# SCH_Dashboy_camera_NiMH_2023-03-21.net
KiCad netlist of a schematic drawn in EasyEDA
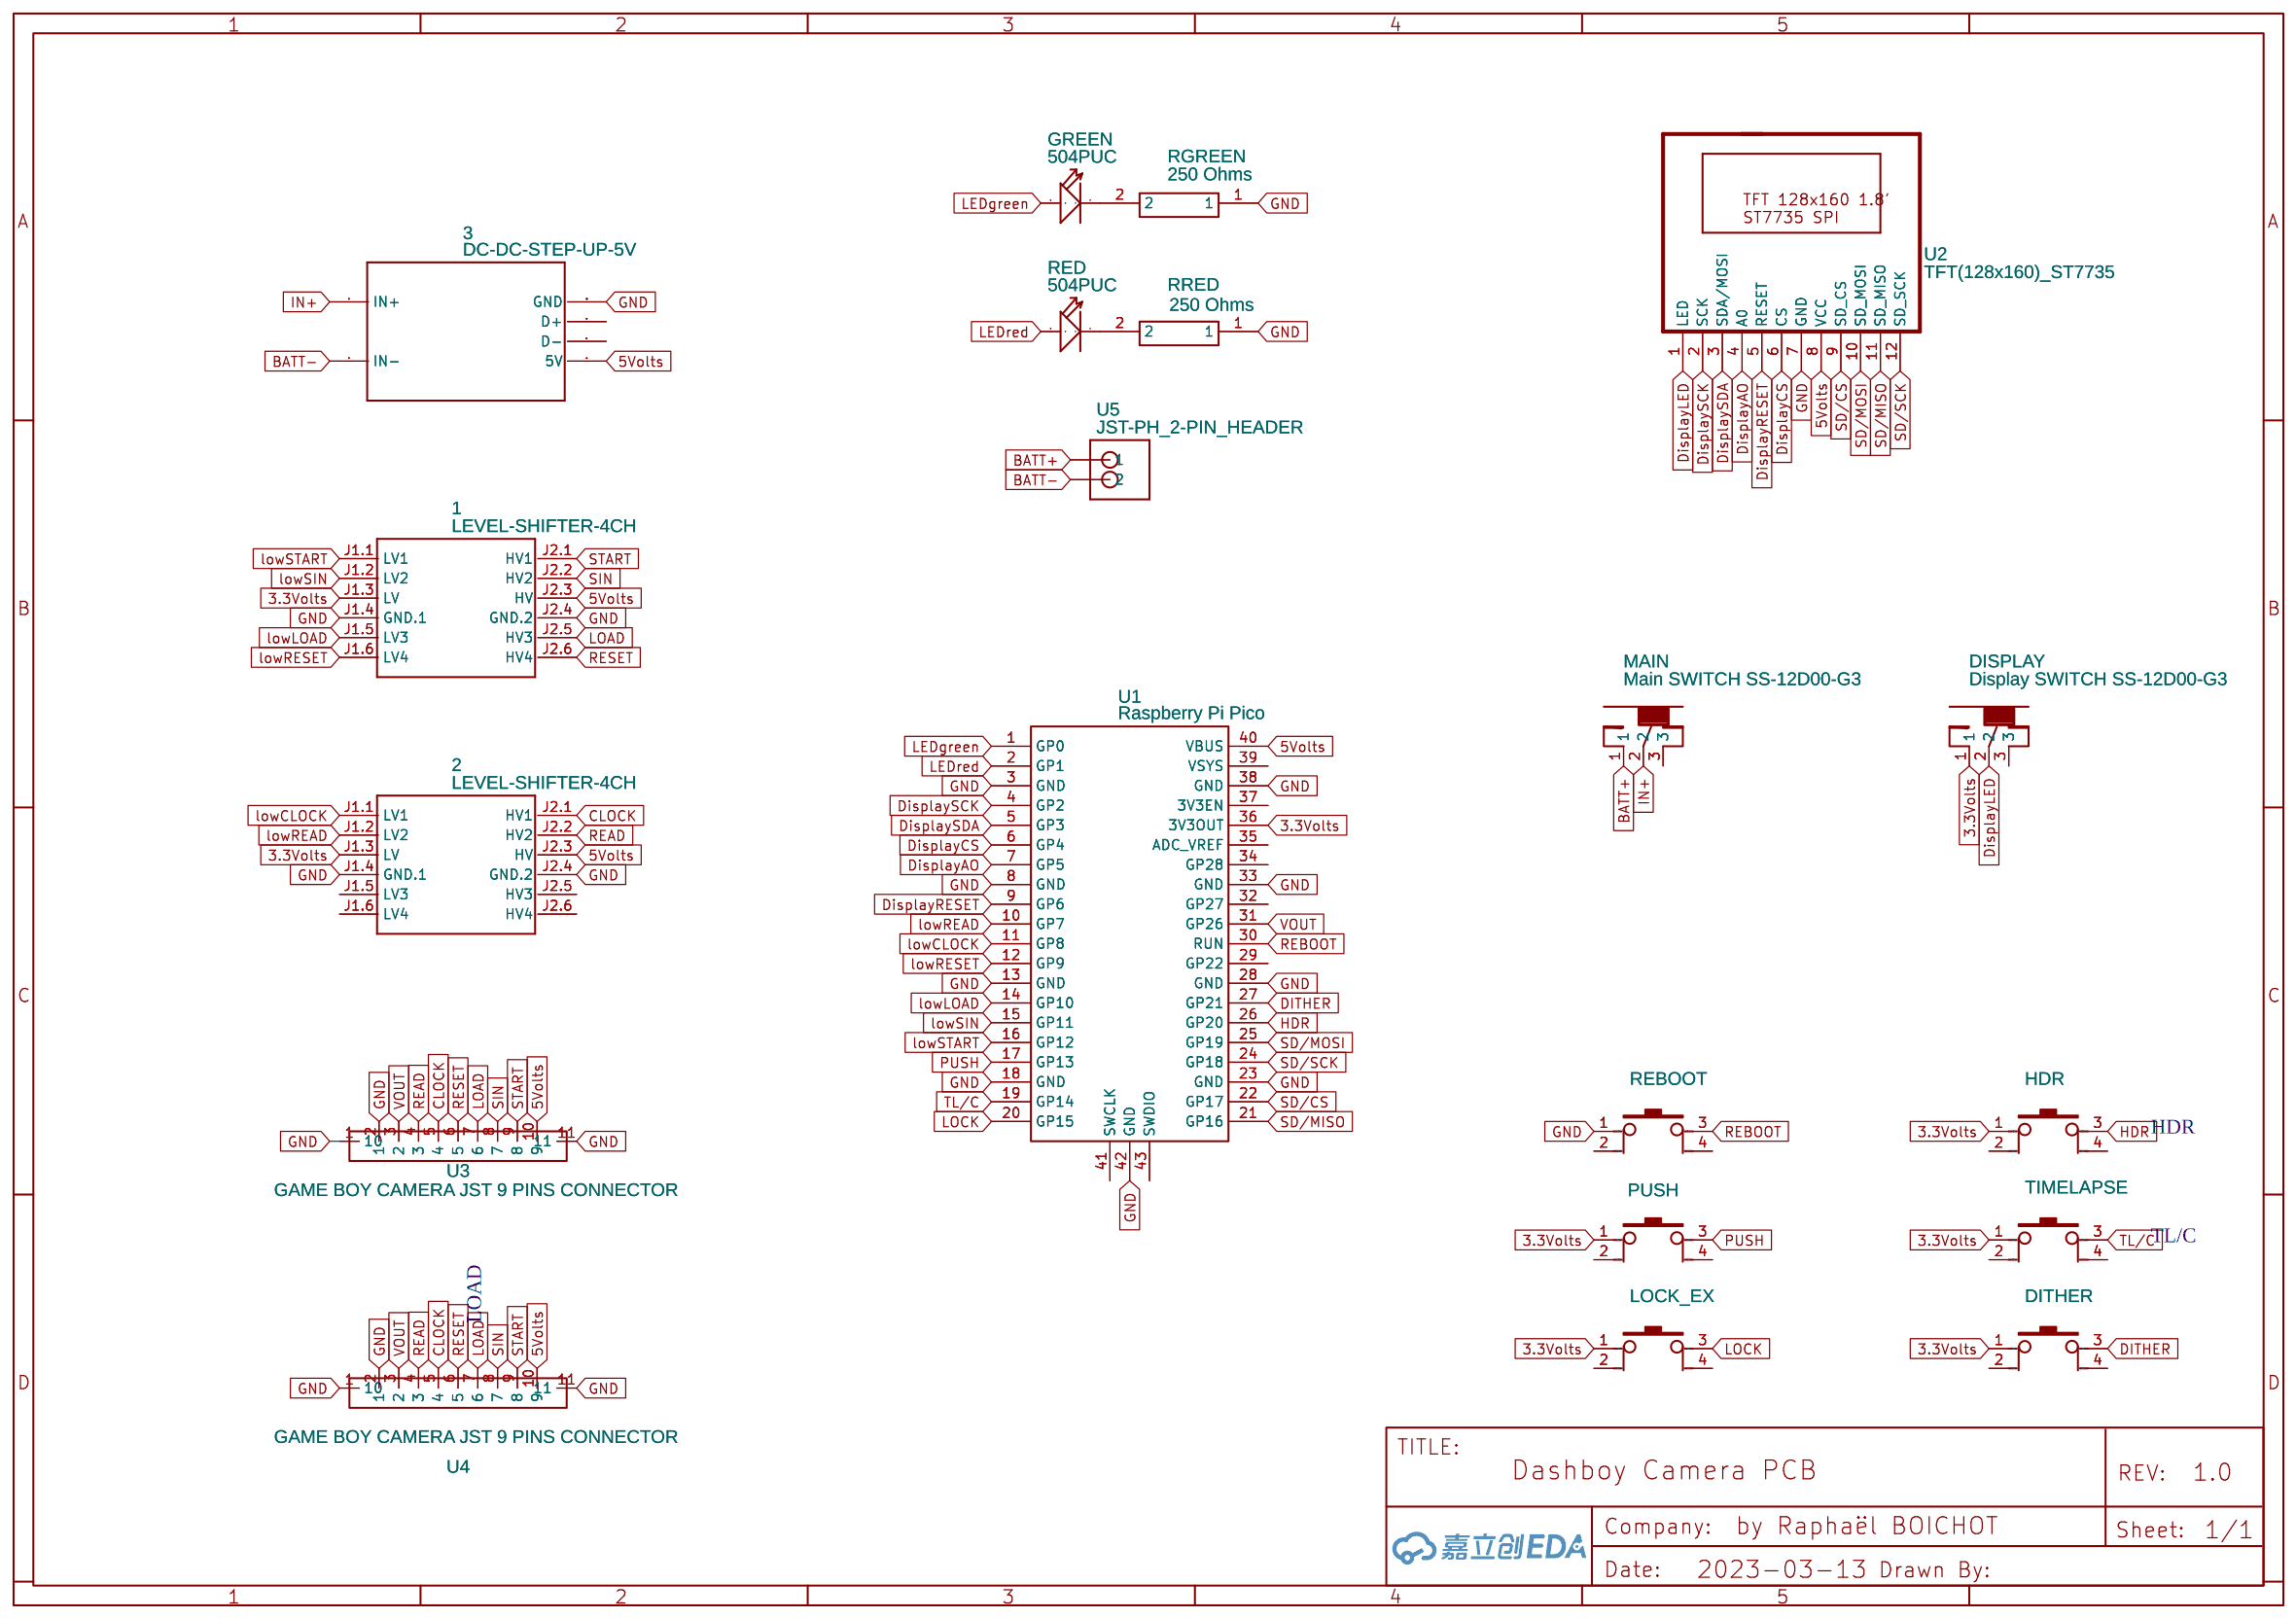
[diagram p0: schematic sheet]

(export (version "E")
  (design (tool "Eeschema 10.0.6"))
  (components
    (comp (ref "1") (value "LEVEL-SHIFTER-4CH") (libsource (lib "") (part "LEVEL-SHIFTER-4CH")))
    (comp (ref "2") (value "LEVEL-SHIFTER-4CH") (libsource (lib "") (part "LEVEL-SHIFTER-4CH")))
    (comp (ref "3") (value "DC-DC-STEP-UP-5V") (libsource (lib "") (part "DC-DC-STEP-UP-5V")))
    (comp (ref "DISPLAY")
      (value "Display SWITCH SS-12D00-G3")
      (fields (field (name "BOM_Manufacturer Part") "TOGGLE SWITCH SS-12D00-G3"))
      (libsource (lib "") (part "TOGGLE SWITCH SS-12D00-G3_1"))
    )
    (comp (ref "DITHER")
      (value "BoutonPoussoir")
      (fields
        (field (name "BOM_Manufacturer Part") "button6*6*8")
        (field (name "BOM_Supplier Part") "C59982")
      )
      (libsource (lib "") (part "BoutonPoussoir_5"))
    )
    (comp (ref "GREEN") (value "504PUC") (libsource (lib "") (part "504PUC_1")))
    (comp (ref "HDR")
      (value "BoutonPoussoir")
      (fields
        (field (name "BOM_Manufacturer Part") "button6*6*8")
        (field (name "BOM_Supplier Part") "C59982")
      )
      (libsource (lib "") (part "BoutonPoussoir_4"))
    )
    (comp (ref "LOCK_EX")
      (value "BoutonPoussoir")
      (fields
        (field (name "BOM_Manufacturer Part") "button6*6*8")
        (field (name "BOM_Supplier Part") "C59982")
      )
      (libsource (lib "") (part "BoutonPoussoir_2"))
    )
    (comp (ref "MAIN")
      (value "Main SWITCH SS-12D00-G3")
      (fields (field (name "BOM_Manufacturer Part") "TOGGLE SWITCH SS-12D00-G3"))
      (libsource (lib "") (part "TOGGLE SWITCH SS-12D00-G3"))
    )
    (comp (ref "PUSH")
      (value "BoutonPoussoir")
      (fields
        (field (name "BOM_Manufacturer Part") "button6*6*8")
        (field (name "BOM_Supplier Part") "C59982")
      )
      (libsource (lib "") (part "BoutonPoussoir_1"))
    )
    (comp (ref "REBOOT")
      (value "BoutonPoussoir")
      (fields
        (field (name "BOM_Manufacturer Part") "button6*6*8")
        (field (name "BOM_Supplier Part") "C59982")
      )
      (libsource (lib "") (part "BoutonPoussoir"))
    )
    (comp (ref "RED") (value "504PUC") (libsource (lib "") (part "504PUC")))
    (comp (ref "RGREEN") (value "250 Ohms") (libsource (lib "") (part "RESITOR")))
    (comp (ref "RRED") (value "250 Ohms") (libsource (lib "") (part "RESITOR_1")))
    (comp (ref "TIMELAPSE")
      (value "BoutonPoussoir")
      (fields
        (field (name "BOM_Manufacturer Part") "button6*6*8")
        (field (name "BOM_Supplier Part") "C59982")
      )
      (libsource (lib "") (part "BoutonPoussoir_3"))
    )
    (comp (ref "U1") (value "Raspberry Pi Pico") (libsource (lib "") (part "Raspberry Pi Pico")))
    (comp (ref "U2") (value "TFT(128x160)_ST7735") (libsource (lib "") (part "TFT(128x160)_ST7735")))
    (comp (ref "U3")
      (value "GAME BOY CAMERA JST 9 PINS CONNECTOR")
      (libsource (lib "") (part "GAME BOY CAMERA JST 9 PINS CONNECTOR"))
    )
    (comp (ref "U4")
      (value "GAME BOY CAMERA JST 9 PINS CONNECTOR")
      (libsource (lib "") (part "GAME BOY CAMERA JST 9 PINS CONNECTOR"))
    )
    (comp (ref "U5") (value "JST-PH_2-PIN_HEADER") (libsource (lib "") (part "JST-PH_2-PIN_HEADER")))
  )
  (nets
    (net (code "1") (name "3.3Volts") (class "Default")
      (node (ref "1") (pin "J1.3") (pinfunction "LV_J1.3") (pintype "bidirectional"))
      (node (ref "2") (pin "J1.3") (pinfunction "LV_J1.3") (pintype "bidirectional"))
      (node (ref "DISPLAY") (pin "1") (pinfunction "1_1") (pintype "bidirectional"))
      (node (ref "DITHER") (pin "1") (pinfunction "1_1") (pintype "input"))
      (node (ref "HDR") (pin "1") (pinfunction "1_1") (pintype "input"))
      (node (ref "LOCK_EX") (pin "1") (pinfunction "1_1") (pintype "input"))
      (node (ref "PUSH") (pin "1") (pinfunction "1_1") (pintype "input"))
      (node (ref "TIMELAPSE") (pin "1") (pinfunction "1_1") (pintype "input"))
      (node (ref "U1") (pin "36") (pinfunction "3V3OUT_36") (pintype "unspecified"))
    )
    (net (code "2") (name "5Volts") (class "Default")
      (node (ref "1") (pin "J2.3") (pinfunction "HV_J2.3") (pintype "bidirectional"))
      (node (ref "2") (pin "J2.3") (pinfunction "HV_J2.3") (pintype "bidirectional"))
      (node (ref "3") (pin "5V") (pinfunction "5V_5V") (pintype "bidirectional"))
      (node (ref "U1") (pin "40") (pinfunction "VBUS_40") (pintype "unspecified"))
      (node (ref "U2") (pin "8") (pinfunction "VCC_8") (pintype "input"))
      (node (ref "U3") (pin "10") (pinfunction "9_10") (pintype "unspecified"))
      (node (ref "U4") (pin "10") (pinfunction "9_10") (pintype "unspecified"))
    )
    (net (code "3") (name "BATT+") (class "Default")
      (node (ref "MAIN") (pin "1") (pinfunction "1_1") (pintype "bidirectional"))
      (node (ref "U5") (pin "P1") (pinfunction "1_P1") (pintype "unspecified"))
    )
    (net (code "4") (name "BATT-") (class "Default")
      (node (ref "3") (pin "IN-") (pinfunction "IN-_IN-") (pintype "bidirectional"))
      (node (ref "U5") (pin "P2") (pinfunction "2_P2") (pintype "unspecified"))
    )
    (net (code "5") (name "CLOCK") (class "Default")
      (node (ref "2") (pin "J2.1") (pinfunction "HV1_J2.1") (pintype "bidirectional"))
      (node (ref "U3") (pin "5") (pinfunction "4_5") (pintype "unspecified"))
      (node (ref "U4") (pin "5") (pinfunction "4_5") (pintype "unspecified"))
    )
    (net (code "6") (name "DITHER") (class "Default")
      (node (ref "DITHER") (pin "3") (pinfunction "3_3") (pintype "input"))
      (node (ref "U1") (pin "27") (pinfunction "GP21_27") (pintype "unspecified"))
    )
    (net (code "7") (name "DisplayAO") (class "Default")
      (node (ref "U1") (pin "7") (pinfunction "GP5_7") (pintype "unspecified"))
      (node (ref "U2") (pin "4") (pinfunction "A0_4") (pintype "input"))
    )
    (net (code "8") (name "DisplayCS") (class "Default")
      (node (ref "U1") (pin "6") (pinfunction "GP4_6") (pintype "unspecified"))
      (node (ref "U2") (pin "6") (pinfunction "CS_6") (pintype "input"))
    )
    (net (code "9") (name "DisplayLED") (class "Default")
      (node (ref "DISPLAY") (pin "2") (pinfunction "2_2") (pintype "bidirectional"))
      (node (ref "U2") (pin "1") (pinfunction "LED_1") (pintype "passive"))
    )
    (net (code "10") (name "DisplayRESET") (class "Default")
      (node (ref "U1") (pin "9") (pinfunction "GP6_9") (pintype "unspecified"))
      (node (ref "U2") (pin "5") (pinfunction "RESET_5") (pintype "input"))
    )
    (net (code "11") (name "DisplaySCK") (class "Default")
      (node (ref "U1") (pin "4") (pinfunction "GP2_4") (pintype "unspecified"))
      (node (ref "U2") (pin "2") (pinfunction "SCK_2") (pintype "output"))
    )
    (net (code "12") (name "DisplaySDA") (class "Default")
      (node (ref "U1") (pin "5") (pinfunction "GP3_5") (pintype "unspecified"))
      (node (ref "U2") (pin "3") (pinfunction "SDA/MOSI_3") (pintype "input"))
    )
    (net (code "13") (name "GND") (class "Default")
      (node (ref "1") (pin "J1.4") (pinfunction "GND.1_J1.4") (pintype "bidirectional"))
      (node (ref "1") (pin "J2.4") (pinfunction "GND.2_J2.4") (pintype "bidirectional"))
      (node (ref "2") (pin "J1.4") (pinfunction "GND.1_J1.4") (pintype "bidirectional"))
      (node (ref "2") (pin "J2.4") (pinfunction "GND.2_J2.4") (pintype "bidirectional"))
      (node (ref "3") (pin "GND") (pinfunction "GND_GND") (pintype "bidirectional"))
      (node (ref "REBOOT") (pin "1") (pinfunction "1_1") (pintype "input"))
      (node (ref "RGREEN") (pin "1") (pinfunction "1_1") (pintype "unspecified"))
      (node (ref "RRED") (pin "1") (pinfunction "1_1") (pintype "unspecified"))
      (node (ref "U1") (pin "13") (pinfunction "GND_13") (pintype "unspecified"))
      (node (ref "U1") (pin "18") (pinfunction "GND_18") (pintype "unspecified"))
      (node (ref "U1") (pin "23") (pinfunction "GND_23") (pintype "unspecified"))
      (node (ref "U1") (pin "28") (pinfunction "GND_28") (pintype "unspecified"))
      (node (ref "U1") (pin "3") (pinfunction "GND_3") (pintype "unspecified"))
      (node (ref "U1") (pin "33") (pinfunction "GND_33") (pintype "unspecified"))
      (node (ref "U1") (pin "38") (pinfunction "GND_38") (pintype "unspecified"))
      (node (ref "U1") (pin "42") (pinfunction "GND_42") (pintype "unspecified"))
      (node (ref "U1") (pin "8") (pinfunction "GND_8") (pintype "unspecified"))
      (node (ref "U2") (pin "7") (pinfunction "GND_7") (pintype "unspecified"))
      (node (ref "U3") (pin "1") (pinfunction "10_1") (pintype "unspecified"))
      (node (ref "U3") (pin "11") (pinfunction "11_11") (pintype "unspecified"))
      (node (ref "U3") (pin "2") (pinfunction "1_2") (pintype "unspecified"))
      (node (ref "U4") (pin "1") (pinfunction "10_1") (pintype "unspecified"))
      (node (ref "U4") (pin "11") (pinfunction "11_11") (pintype "unspecified"))
      (node (ref "U4") (pin "2") (pinfunction "1_2") (pintype "unspecified"))
    )
    (net (code "14") (name "HDR") (class "Default")
      (node (ref "HDR") (pin "3") (pinfunction "3_3") (pintype "input"))
      (node (ref "U1") (pin "26") (pinfunction "GP20_26") (pintype "unspecified"))
    )
    (net (code "15") (name "IN+") (class "Default")
      (node (ref "3") (pin "IN+") (pinfunction "IN+_IN+") (pintype "bidirectional"))
      (node (ref "MAIN") (pin "2") (pinfunction "2_2") (pintype "bidirectional"))
    )
    (net (code "16") (name "LEDgreen") (class "Default")
      (node (ref "GREEN") (pin "+") (pinfunction "+_+") (pintype "unspecified"))
      (node (ref "U1") (pin "1") (pinfunction "GP0_1") (pintype "unspecified"))
    )
    (net (code "17") (name "LEDred") (class "Default")
      (node (ref "RED") (pin "+") (pinfunction "+_+") (pintype "unspecified"))
      (node (ref "U1") (pin "2") (pinfunction "GP1_2") (pintype "unspecified"))
    )
    (net (code "18") (name "LOAD") (class "Default")
      (node (ref "1") (pin "J2.5") (pinfunction "HV3_J2.5") (pintype "bidirectional"))
      (node (ref "U3") (pin "7") (pinfunction "6_7") (pintype "unspecified"))
      (node (ref "U4") (pin "7") (pinfunction "6_7") (pintype "unspecified"))
    )
    (net (code "19") (name "LOCK") (class "Default")
      (node (ref "LOCK_EX") (pin "3") (pinfunction "3_3") (pintype "input"))
      (node (ref "U1") (pin "20") (pinfunction "GP15_20") (pintype "unspecified"))
    )
    (net (code "20") (name "Net-(GREEN-Pad-)") (class "Default")
      (node (ref "GREEN") (pin "-") (pinfunction "-_-") (pintype "unspecified"))
      (node (ref "RGREEN") (pin "2") (pinfunction "2_2") (pintype "unspecified"))
    )
    (net (code "21") (name "Net-(RED-Pad-)") (class "Default")
      (node (ref "RED") (pin "-") (pinfunction "-_-") (pintype "unspecified"))
      (node (ref "RRED") (pin "2") (pinfunction "2_2") (pintype "unspecified"))
    )
    (net (code "22") (name "PUSH") (class "Default")
      (node (ref "PUSH") (pin "3") (pinfunction "3_3") (pintype "input"))
      (node (ref "U1") (pin "17") (pinfunction "GP13_17") (pintype "unspecified"))
    )
    (net (code "23") (name "READ") (class "Default")
      (node (ref "2") (pin "J2.2") (pinfunction "HV2_J2.2") (pintype "bidirectional"))
      (node (ref "U3") (pin "4") (pinfunction "3_4") (pintype "unspecified"))
      (node (ref "U4") (pin "4") (pinfunction "3_4") (pintype "unspecified"))
    )
    (net (code "24") (name "REBOOT") (class "Default")
      (node (ref "REBOOT") (pin "3") (pinfunction "3_3") (pintype "input"))
      (node (ref "U1") (pin "30") (pinfunction "RUN_30") (pintype "unspecified"))
    )
    (net (code "25") (name "RESET") (class "Default")
      (node (ref "1") (pin "J2.6") (pinfunction "HV4_J2.6") (pintype "bidirectional"))
      (node (ref "U3") (pin "6") (pinfunction "5_6") (pintype "unspecified"))
      (node (ref "U4") (pin "6") (pinfunction "5_6") (pintype "unspecified"))
    )
    (net (code "26") (name "SD{slash}CS") (class "Default")
      (node (ref "U1") (pin "22") (pinfunction "GP17_22") (pintype "unspecified"))
      (node (ref "U2") (pin "9") (pinfunction "SD_CS_9") (pintype "input"))
    )
    (net (code "27") (name "SD{slash}MISO") (class "Default")
      (node (ref "U1") (pin "21") (pinfunction "GP16_21") (pintype "unspecified"))
      (node (ref "U2") (pin "11") (pinfunction "SD_MISO_11") (pintype "input"))
    )
    (net (code "28") (name "SD{slash}MOSI") (class "Default")
      (node (ref "U1") (pin "25") (pinfunction "GP19_25") (pintype "unspecified"))
      (node (ref "U2") (pin "10") (pinfunction "SD_MOSI_10") (pintype "input"))
    )
    (net (code "29") (name "SD{slash}SCK") (class "Default")
      (node (ref "U1") (pin "24") (pinfunction "GP18_24") (pintype "unspecified"))
      (node (ref "U2") (pin "12") (pinfunction "SD_SCK_12") (pintype "input"))
    )
    (net (code "30") (name "SIN") (class "Default")
      (node (ref "1") (pin "J2.2") (pinfunction "HV2_J2.2") (pintype "bidirectional"))
      (node (ref "U3") (pin "8") (pinfunction "7_8") (pintype "unspecified"))
      (node (ref "U4") (pin "8") (pinfunction "7_8") (pintype "unspecified"))
    )
    (net (code "31") (name "START") (class "Default")
      (node (ref "1") (pin "J2.1") (pinfunction "HV1_J2.1") (pintype "bidirectional"))
      (node (ref "U3") (pin "9") (pinfunction "8_9") (pintype "unspecified"))
      (node (ref "U4") (pin "9") (pinfunction "8_9") (pintype "unspecified"))
    )
    (net (code "32") (name "TL{slash}C") (class "Default")
      (node (ref "TIMELAPSE") (pin "3") (pinfunction "3_3") (pintype "input"))
      (node (ref "U1") (pin "19") (pinfunction "GP14_19") (pintype "unspecified"))
    )
    (net (code "33") (name "VOUT") (class "Default")
      (node (ref "U1") (pin "31") (pinfunction "GP26_31") (pintype "unspecified"))
      (node (ref "U3") (pin "3") (pinfunction "2_3") (pintype "unspecified"))
      (node (ref "U4") (pin "3") (pinfunction "2_3") (pintype "unspecified"))
    )
    (net (code "34") (name "lowCLOCK") (class "Default")
      (node (ref "2") (pin "J1.1") (pinfunction "LV1_J1.1") (pintype "bidirectional"))
      (node (ref "U1") (pin "11") (pinfunction "GP8_11") (pintype "unspecified"))
    )
    (net (code "35") (name "lowLOAD") (class "Default")
      (node (ref "1") (pin "J1.5") (pinfunction "LV3_J1.5") (pintype "bidirectional"))
      (node (ref "U1") (pin "14") (pinfunction "GP10_14") (pintype "unspecified"))
    )
    (net (code "36") (name "lowREAD") (class "Default")
      (node (ref "2") (pin "J1.2") (pinfunction "LV2_J1.2") (pintype "bidirectional"))
      (node (ref "U1") (pin "10") (pinfunction "GP7_10") (pintype "unspecified"))
    )
    (net (code "37") (name "lowRESET") (class "Default")
      (node (ref "1") (pin "J1.6") (pinfunction "LV4_J1.6") (pintype "bidirectional"))
      (node (ref "U1") (pin "12") (pinfunction "GP9_12") (pintype "unspecified"))
    )
    (net (code "38") (name "lowSIN") (class "Default")
      (node (ref "1") (pin "J1.2") (pinfunction "LV2_J1.2") (pintype "bidirectional"))
      (node (ref "U1") (pin "15") (pinfunction "GP11_15") (pintype "unspecified"))
    )
    (net (code "39") (name "lowSTART") (class "Default")
      (node (ref "1") (pin "J1.1") (pinfunction "LV1_J1.1") (pintype "bidirectional"))
      (node (ref "U1") (pin "16") (pinfunction "GP12_16") (pintype "unspecified"))
    )
    (net (code "40") (name "unconnected-(2-HV3-PadJ2.5)") (class "Default")
      (node (ref "2") (pin "J2.5") (pinfunction "HV3_J2.5") (pintype "bidirectional"))
    )
    (net (code "41") (name "unconnected-(2-HV4-PadJ2.6)") (class "Default")
      (node (ref "2") (pin "J2.6") (pinfunction "HV4_J2.6") (pintype "bidirectional"))
    )
    (net (code "42") (name "unconnected-(2-LV3-PadJ1.5)") (class "Default")
      (node (ref "2") (pin "J1.5") (pinfunction "LV3_J1.5") (pintype "bidirectional"))
    )
    (net (code "43") (name "unconnected-(2-LV4-PadJ1.6)") (class "Default")
      (node (ref "2") (pin "J1.6") (pinfunction "LV4_J1.6") (pintype "bidirectional"))
    )
    (net (code "44") (name "unconnected-(3-PadD+)") (class "Default")
      (node (ref "3") (pin "D+") (pinfunction "D+_D+") (pintype "bidirectional"))
    )
    (net (code "45") (name "unconnected-(3-PadD-)") (class "Default")
      (node (ref "3") (pin "D-") (pinfunction "D-_D-") (pintype "bidirectional"))
    )
    (net (code "46") (name "unconnected-(DISPLAY-Pad3)") (class "Default")
      (node (ref "DISPLAY") (pin "3") (pinfunction "3_3") (pintype "unspecified"))
    )
    (net (code "47") (name "unconnected-(DITHER-Pad2)") (class "Default")
      (node (ref "DITHER") (pin "2") (pinfunction "2_2") (pintype "input"))
    )
    (net (code "48") (name "unconnected-(DITHER-Pad4)") (class "Default")
      (node (ref "DITHER") (pin "4") (pinfunction "4_4") (pintype "input"))
    )
    (net (code "49") (name "unconnected-(HDR-Pad2)") (class "Default")
      (node (ref "HDR") (pin "2") (pinfunction "2_2") (pintype "input"))
    )
    (net (code "50") (name "unconnected-(HDR-Pad4)") (class "Default")
      (node (ref "HDR") (pin "4") (pinfunction "4_4") (pintype "input"))
    )
    (net (code "51") (name "unconnected-(LOCK_EX-Pad2)") (class "Default")
      (node (ref "LOCK_EX") (pin "2") (pinfunction "2_2") (pintype "input"))
    )
    (net (code "52") (name "unconnected-(LOCK_EX-Pad4)") (class "Default")
      (node (ref "LOCK_EX") (pin "4") (pinfunction "4_4") (pintype "input"))
    )
    (net (code "53") (name "unconnected-(MAIN-Pad3)") (class "Default")
      (node (ref "MAIN") (pin "3") (pinfunction "3_3") (pintype "unspecified"))
    )
    (net (code "54") (name "unconnected-(PUSH-Pad2)") (class "Default")
      (node (ref "PUSH") (pin "2") (pinfunction "2_2") (pintype "input"))
    )
    (net (code "55") (name "unconnected-(PUSH-Pad4)") (class "Default")
      (node (ref "PUSH") (pin "4") (pinfunction "4_4") (pintype "input"))
    )
    (net (code "56") (name "unconnected-(REBOOT-Pad2)") (class "Default")
      (node (ref "REBOOT") (pin "2") (pinfunction "2_2") (pintype "input"))
    )
    (net (code "57") (name "unconnected-(REBOOT-Pad4)") (class "Default")
      (node (ref "REBOOT") (pin "4") (pinfunction "4_4") (pintype "input"))
    )
    (net (code "58") (name "unconnected-(TIMELAPSE-Pad2)") (class "Default")
      (node (ref "TIMELAPSE") (pin "2") (pinfunction "2_2") (pintype "input"))
    )
    (net (code "59") (name "unconnected-(TIMELAPSE-Pad4)") (class "Default")
      (node (ref "TIMELAPSE") (pin "4") (pinfunction "4_4") (pintype "input"))
    )
    (net (code "60") (name "unconnected-(U1-3V3EN-Pad37)") (class "Default")
      (node (ref "U1") (pin "37") (pinfunction "3V3EN_37") (pintype "unspecified"))
    )
    (net (code "61") (name "unconnected-(U1-ADC_VREF-Pad35)") (class "Default")
      (node (ref "U1") (pin "35") (pinfunction "ADC_VREF_35") (pintype "unspecified"))
    )
    (net (code "62") (name "unconnected-(U1-GP22-Pad29)") (class "Default")
      (node (ref "U1") (pin "29") (pinfunction "GP22_29") (pintype "unspecified"))
    )
    (net (code "63") (name "unconnected-(U1-GP27-Pad32)") (class "Default")
      (node (ref "U1") (pin "32") (pinfunction "GP27_32") (pintype "unspecified"))
    )
    (net (code "64") (name "unconnected-(U1-GP28-Pad34)") (class "Default")
      (node (ref "U1") (pin "34") (pinfunction "GP28_34") (pintype "unspecified"))
    )
    (net (code "65") (name "unconnected-(U1-SWCLK-Pad41)") (class "Default")
      (node (ref "U1") (pin "41") (pinfunction "SWCLK_41") (pintype "unspecified"))
    )
    (net (code "66") (name "unconnected-(U1-SWDIO-Pad43)") (class "Default")
      (node (ref "U1") (pin "43") (pinfunction "SWDIO_43") (pintype "unspecified"))
    )
    (net (code "67") (name "unconnected-(U1-VSYS-Pad39)") (class "Default")
      (node (ref "U1") (pin "39") (pinfunction "VSYS_39") (pintype "unspecified"))
    )
  )
)
